# TLCduino.net
KiCad netlist of a schematic drawn in EAGLE
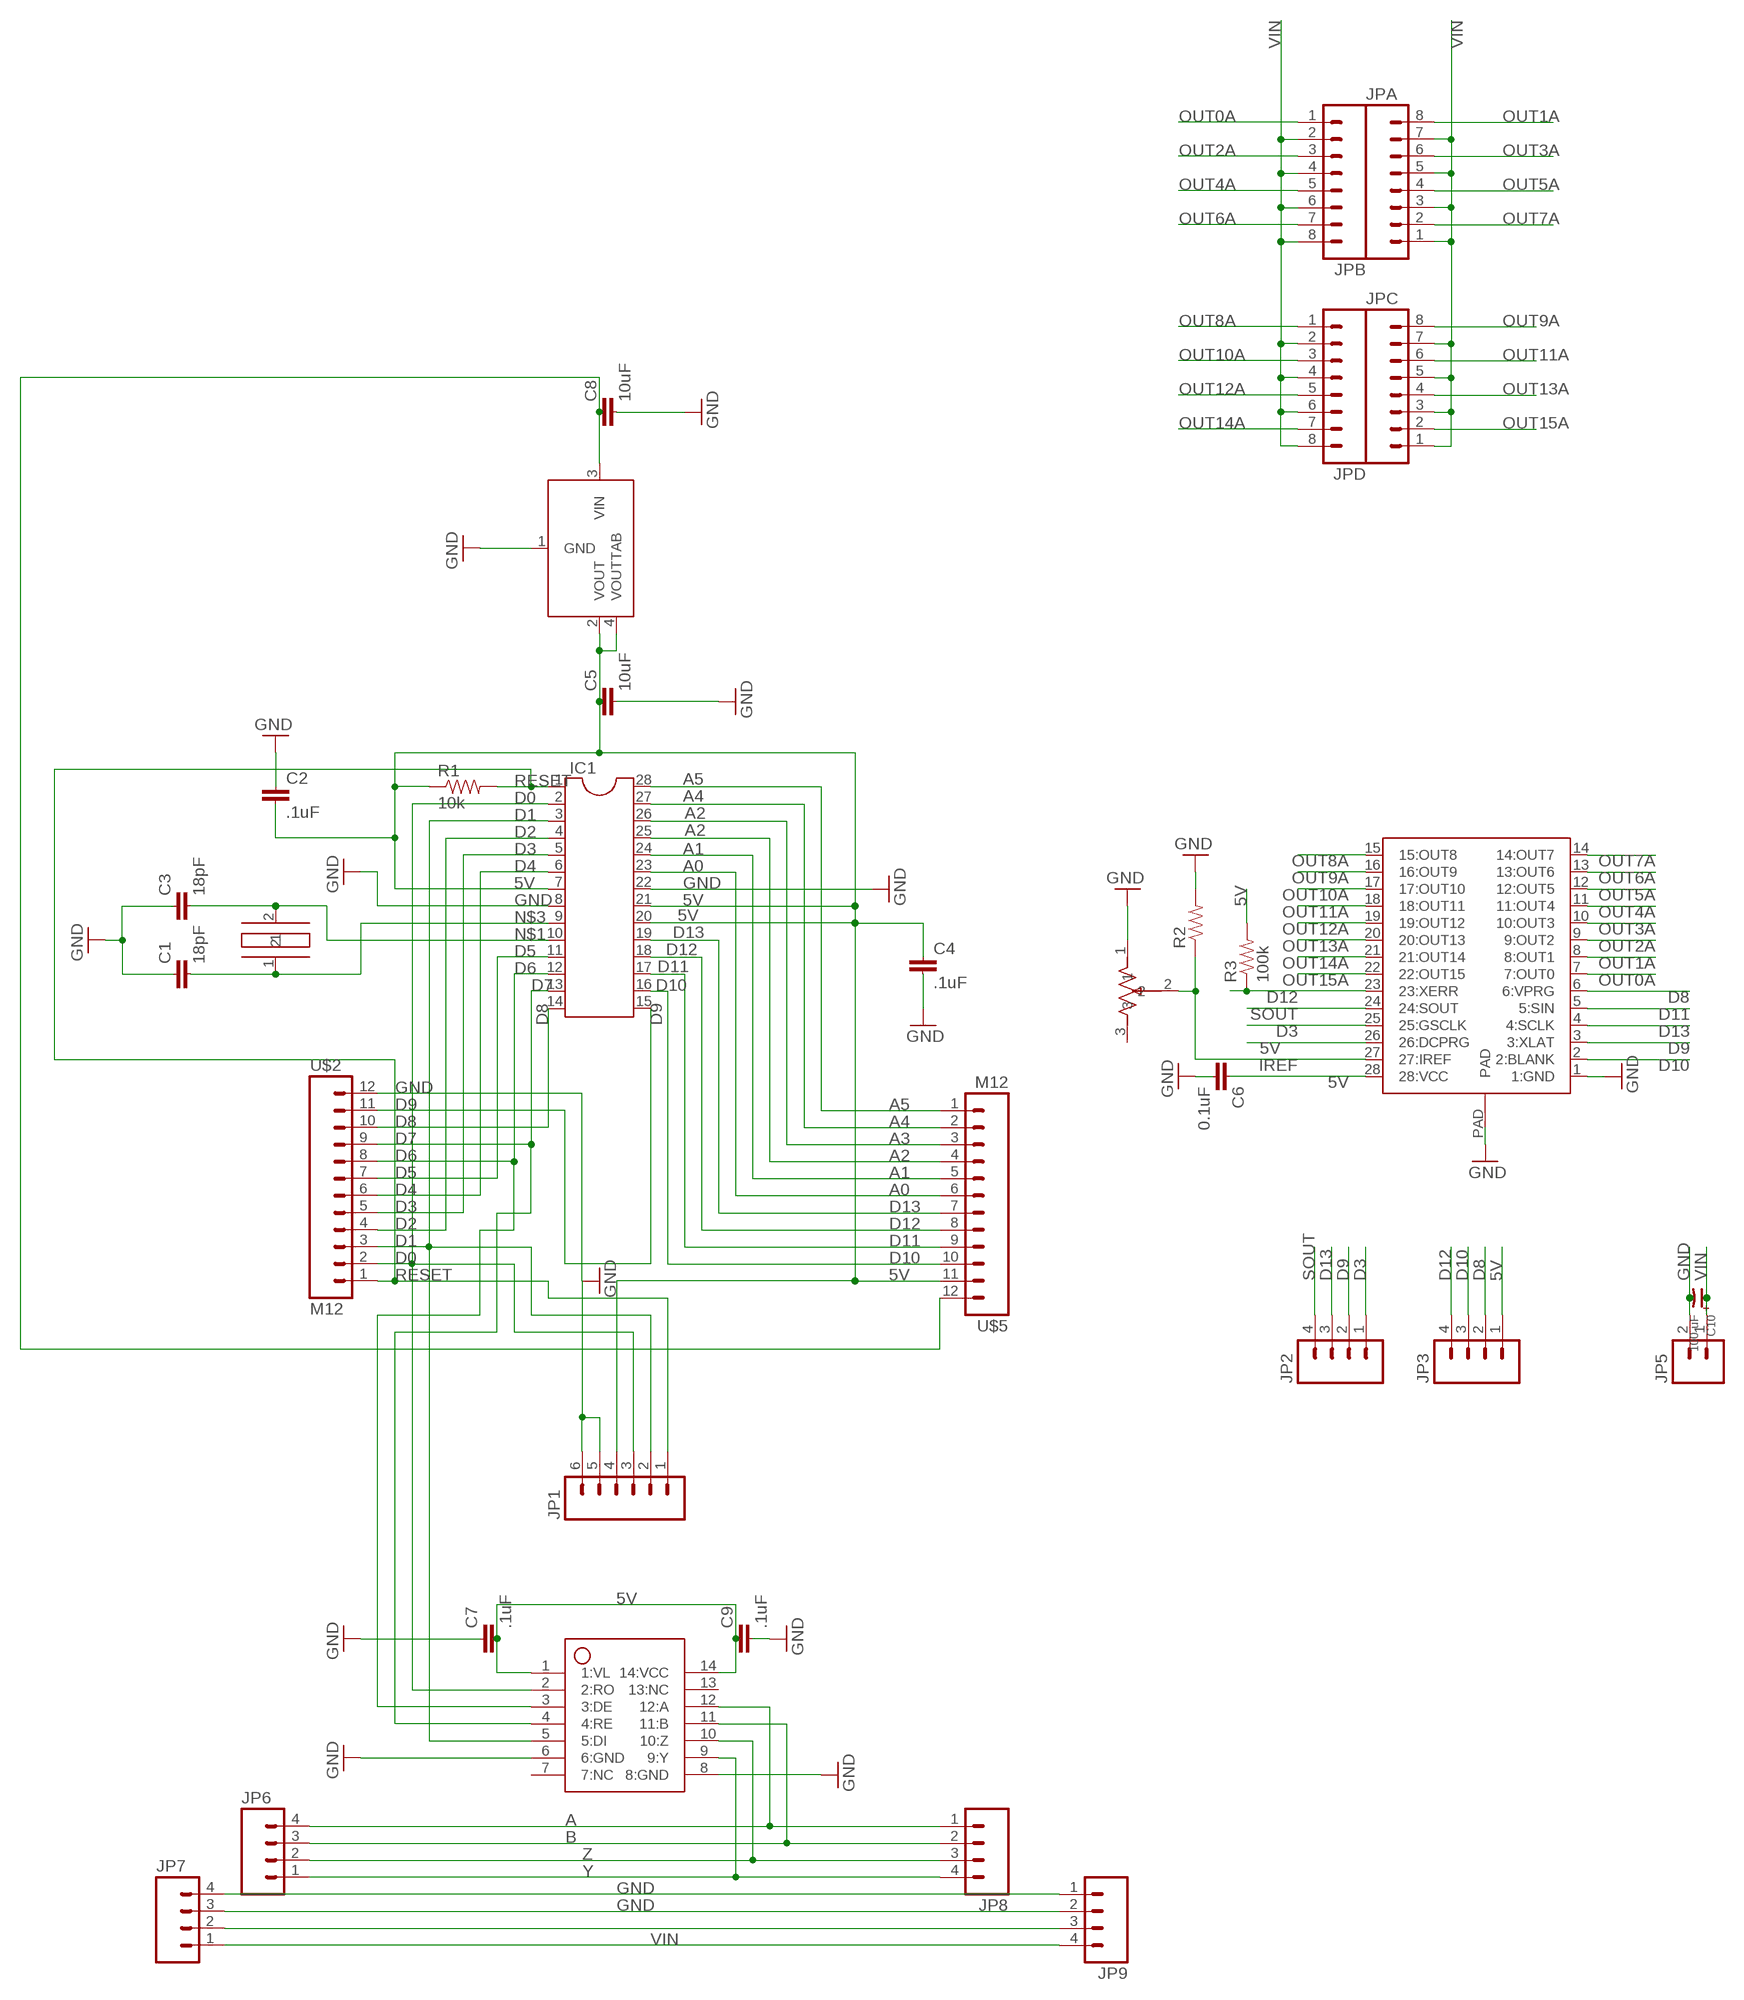
[diagram p0: schematic, sheet 1]

(export (version "E")
  (design (tool "Eeschema 10.0.6"))
  (components
    (comp (ref "5V")
      (value "ZLDO1117")
      (footprint "eagle-import:ZLDO1117")
      (libsource (lib "eagle-import") (part "ZLDO1117"))
    )
    (comp (ref "C1")
      (value "18pF")
      (footprint "eagle-import:0603-CAP")
      (libsource (lib "eagle-import") (part "CAP0603-CAP"))
    )
    (comp (ref "C2")
      (value ".1uF")
      (footprint "eagle-import:0805")
      (libsource (lib "eagle-import") (part "CAP0805"))
    )
    (comp (ref "C3")
      (value "18pF")
      (footprint "eagle-import:0603-CAP")
      (libsource (lib "eagle-import") (part "CAP0603-CAP"))
    )
    (comp (ref "C4")
      (value ".1uF")
      (footprint "eagle-import:0805")
      (libsource (lib "eagle-import") (part "CAP0805"))
    )
    (comp (ref "C5")
      (value "10uF")
      (footprint "eagle-import:1206")
      (libsource (lib "eagle-import") (part "CAP1206"))
    )
    (comp (ref "C6")
      (value "0.1uF")
      (footprint "eagle-import:0805")
      (libsource (lib "eagle-import") (part "CAP0805"))
    )
    (comp (ref "C7")
      (value ".1uF")
      (footprint "eagle-import:0805")
      (libsource (lib "eagle-import") (part "CAP0805"))
    )
    (comp (ref "C8")
      (value "10uF")
      (footprint "eagle-import:1206")
      (libsource (lib "eagle-import") (part "CAP1206"))
    )
    (comp (ref "C9")
      (value ".1uF")
      (footprint "eagle-import:0805")
      (libsource (lib "eagle-import") (part "CAP0805"))
    )
    (comp (ref "C10")
      (value "100 uF")
      (footprint "eagle-import:5X11MMCAP")
      (libsource (lib "eagle-import") (part "CAPPOL-5X11"))
    )
    (comp (ref "IC1")
      (value "DIL28-3")
      (footprint "eagle-import:DIL28-3")
      (libsource (lib "eagle-import") (part "DIL28-3"))
    )
    (comp (ref "JP1")
      (value "M06LOCK")
      (footprint "eagle-import:1X06_LOCK")
      (libsource (lib "eagle-import") (part "M06LOCK"))
    )
    (comp (ref "JP2")
      (value "M04LOCK")
      (footprint "eagle-import:1X04_LOCK")
      (libsource (lib "eagle-import") (part "M04LOCK"))
    )
    (comp (ref "JP3")
      (value "M04LOCK")
      (footprint "eagle-import:1X04_LOCK")
      (libsource (lib "eagle-import") (part "M04LOCK"))
    )
    (comp (ref "JP5")
      (value "M02LOCK")
      (footprint "eagle-import:1X02_LOCK")
      (libsource (lib "eagle-import") (part "M02LOCK"))
    )
    (comp (ref "JP6")
      (value "M04LOCK")
      (footprint "eagle-import:1X04_LOCK")
      (libsource (lib "eagle-import") (part "M04LOCK"))
    )
    (comp (ref "JP7")
      (value "M04LOCK")
      (footprint "eagle-import:1X04_LOCK")
      (libsource (lib "eagle-import") (part "M04LOCK"))
    )
    (comp (ref "JP8")
      (value "M04LOCK")
      (footprint "eagle-import:1X04_LOCK")
      (libsource (lib "eagle-import") (part "M04LOCK"))
    )
    (comp (ref "JP9")
      (value "M04LOCK")
      (footprint "eagle-import:1X04_LOCK")
      (libsource (lib "eagle-import") (part "M04LOCK"))
    )
    (comp (ref "JPA")
      (value "M08LOCK")
      (footprint "eagle-import:1X08_LOCK")
      (libsource (lib "eagle-import") (part "M08LOCK"))
    )
    (comp (ref "JPB")
      (value "M08LOCK")
      (footprint "eagle-import:1X08_LOCK")
      (libsource (lib "eagle-import") (part "M08LOCK"))
    )
    (comp (ref "JPC")
      (value "M08LOCK")
      (footprint "eagle-import:1X08_LOCK")
      (libsource (lib "eagle-import") (part "M08LOCK"))
    )
    (comp (ref "JPD")
      (value "M08LOCK")
      (footprint "eagle-import:1X08_LOCK")
      (libsource (lib "eagle-import") (part "M08LOCK"))
    )
    (comp (ref "R1")
      (value "10k")
      (footprint "eagle-import:0805")
      (libsource (lib "eagle-import") (part "RESISTOR"))
    )
    (comp (ref "R2")
      (value "RESISTOR")
      (footprint "eagle-import:0805")
      (libsource (lib "eagle-import") (part "RESISTOR"))
    )
    (comp (ref "R3")
      (value "100k")
      (footprint "eagle-import:0805")
      (libsource (lib "eagle-import") (part "RESISTOR"))
    )
    (comp (ref "U$1")
      (value "HC49US")
      (footprint "eagle-import:HC49US")
      (libsource (lib "eagle-import") (part "HC49US"))
    )
    (comp (ref "U$2")
      (value "M12")
      (footprint "eagle-import:1X12_LOCK")
      (libsource (lib "eagle-import") (part "M12LOCK"))
    )
    (comp (ref "U$3")
      (value "TLC5940")
      (footprint "eagle-import:HTSSOP-28")
      (libsource (lib "eagle-import") (part "TLC5940"))
    )
    (comp (ref "U$4")
      (value "TRIMPOTTC33X-2")
      (footprint "eagle-import:TC33X-2")
      (libsource (lib "eagle-import") (part "TRIMPOTTC33X-2"))
    )
    (comp (ref "U$5")
      (value "M12")
      (footprint "eagle-import:1X12_LOCK")
      (libsource (lib "eagle-import") (part "M12LOCK"))
    )
    (comp (ref "U$6")
      (value "MAX13432")
      (footprint "eagle-import:SO14")
      (libsource (lib "eagle-import") (part "MAX13432"))
    )
  )
  (nets
    (net (code "1") (name "/5V") (class "Default")
      (node (ref "5V") (pin "2") (pinfunction "VOUT_2") (pintype "bidirectional"))
      (node (ref "5V") (pin "4") (pinfunction "VOUTTAB_4") (pintype "bidirectional"))
      (node (ref "C2") (pin "2") (pinfunction "2_2") (pintype "passive"))
      (node (ref "C4") (pin "1") (pinfunction "1_1") (pintype "passive"))
      (node (ref "C5") (pin "1") (pinfunction "1_1") (pintype "passive"))
      (node (ref "C6") (pin "1") (pinfunction "1_1") (pintype "passive"))
      (node (ref "C7") (pin "2") (pinfunction "2_2") (pintype "passive"))
      (node (ref "C9") (pin "1") (pinfunction "1_1") (pintype "passive"))
      (node (ref "IC1") (pin "20") (pinfunction "20_20") (pintype "passive"))
      (node (ref "IC1") (pin "21") (pinfunction "21_21") (pintype "passive"))
      (node (ref "IC1") (pin "7") (pinfunction "7_7") (pintype "passive"))
      (node (ref "JP1") (pin "4") (pinfunction "4_4") (pintype "passive"))
      (node (ref "JP3") (pin "1") (pinfunction "1_1") (pintype "passive"))
      (node (ref "R1") (pin "1") (pinfunction "1_1") (pintype "passive"))
      (node (ref "R3") (pin "2") (pinfunction "2_2") (pintype "passive"))
      (node (ref "U$3") (pin "26") (pinfunction "26:DCPRG_26") (pintype "bidirectional"))
      (node (ref "U$3") (pin "28") (pinfunction "28:VCC_28") (pintype "bidirectional"))
      (node (ref "U$5") (pin "11") (pinfunction "11_11") (pintype "passive"))
      (node (ref "U$6") (pin "1") (pinfunction "1:VL_1") (pintype "bidirectional"))
      (node (ref "U$6") (pin "14") (pinfunction "14:VCC_14") (pintype "bidirectional"))
    )
    (net (code "2") (name "/A") (class "Default")
      (node (ref "JP6") (pin "4") (pinfunction "4_4") (pintype "passive"))
      (node (ref "JP8") (pin "1") (pinfunction "1_1") (pintype "passive"))
      (node (ref "U$6") (pin "12") (pinfunction "12:A_12") (pintype "bidirectional"))
    )
    (net (code "3") (name "/A0") (class "Default")
      (node (ref "IC1") (pin "23") (pinfunction "23_23") (pintype "passive"))
      (node (ref "U$5") (pin "6") (pinfunction "6_6") (pintype "passive"))
    )
    (net (code "4") (name "/A1") (class "Default")
      (node (ref "IC1") (pin "24") (pinfunction "24_24") (pintype "passive"))
      (node (ref "U$5") (pin "5") (pinfunction "5_5") (pintype "passive"))
    )
    (net (code "5") (name "/A2") (class "Default")
      (node (ref "IC1") (pin "25") (pinfunction "25_25") (pintype "passive"))
      (node (ref "U$5") (pin "4") (pinfunction "4_4") (pintype "passive"))
    )
    (net (code "6") (name "/A3") (class "Default")
      (node (ref "IC1") (pin "26") (pinfunction "26_26") (pintype "passive"))
      (node (ref "U$5") (pin "3") (pinfunction "3_3") (pintype "passive"))
    )
    (net (code "7") (name "/A4") (class "Default")
      (node (ref "IC1") (pin "27") (pinfunction "27_27") (pintype "passive"))
      (node (ref "U$5") (pin "2") (pinfunction "2_2") (pintype "passive"))
    )
    (net (code "8") (name "/A5") (class "Default")
      (node (ref "IC1") (pin "28") (pinfunction "28_28") (pintype "passive"))
      (node (ref "U$5") (pin "1") (pinfunction "1_1") (pintype "passive"))
    )
    (net (code "9") (name "/B") (class "Default")
      (node (ref "JP6") (pin "3") (pinfunction "3_3") (pintype "passive"))
      (node (ref "JP8") (pin "2") (pinfunction "2_2") (pintype "passive"))
      (node (ref "U$6") (pin "11") (pinfunction "11:B_11") (pintype "bidirectional"))
    )
    (net (code "10") (name "/D0") (class "Default")
      (node (ref "IC1") (pin "2") (pinfunction "2_2") (pintype "passive"))
      (node (ref "JP1") (pin "3") (pinfunction "3_3") (pintype "passive"))
      (node (ref "U$2") (pin "2") (pinfunction "2_2") (pintype "passive"))
      (node (ref "U$6") (pin "2") (pinfunction "2:RO_2") (pintype "bidirectional"))
    )
    (net (code "11") (name "/D1") (class "Default")
      (node (ref "IC1") (pin "3") (pinfunction "3_3") (pintype "passive"))
      (node (ref "JP1") (pin "2") (pinfunction "2_2") (pintype "passive"))
      (node (ref "U$2") (pin "3") (pinfunction "3_3") (pintype "passive"))
      (node (ref "U$6") (pin "5") (pinfunction "5:DI_5") (pintype "bidirectional"))
    )
    (net (code "12") (name "/D2") (class "Default")
      (node (ref "IC1") (pin "4") (pinfunction "4_4") (pintype "passive"))
      (node (ref "U$2") (pin "4") (pinfunction "4_4") (pintype "passive"))
    )
    (net (code "13") (name "/D3") (class "Default")
      (node (ref "IC1") (pin "5") (pinfunction "5_5") (pintype "passive"))
      (node (ref "JP2") (pin "1") (pinfunction "1_1") (pintype "passive"))
      (node (ref "U$2") (pin "5") (pinfunction "5_5") (pintype "passive"))
      (node (ref "U$3") (pin "25") (pinfunction "25:GSCLK_25") (pintype "bidirectional"))
    )
    (net (code "14") (name "/D4") (class "Default")
      (node (ref "IC1") (pin "6") (pinfunction "6_6") (pintype "passive"))
      (node (ref "U$2") (pin "6") (pinfunction "6_6") (pintype "passive"))
    )
    (net (code "15") (name "/D5") (class "Default")
      (node (ref "IC1") (pin "11") (pinfunction "11_11") (pintype "passive"))
      (node (ref "U$2") (pin "7") (pinfunction "7_7") (pintype "passive"))
    )
    (net (code "16") (name "/D6") (class "Default")
      (node (ref "IC1") (pin "12") (pinfunction "12_12") (pintype "passive"))
      (node (ref "U$2") (pin "8") (pinfunction "8_8") (pintype "passive"))
      (node (ref "U$6") (pin "3") (pinfunction "3:DE_3") (pintype "bidirectional"))
    )
    (net (code "17") (name "/D7") (class "Default")
      (node (ref "IC1") (pin "13") (pinfunction "13_13") (pintype "passive"))
      (node (ref "U$2") (pin "9") (pinfunction "9_9") (pintype "passive"))
      (node (ref "U$6") (pin "4") (pinfunction "4:RE_4") (pintype "bidirectional"))
    )
    (net (code "18") (name "/D8") (class "Default")
      (node (ref "IC1") (pin "14") (pinfunction "14_14") (pintype "passive"))
      (node (ref "JP3") (pin "2") (pinfunction "2_2") (pintype "passive"))
      (node (ref "U$2") (pin "10") (pinfunction "10_10") (pintype "passive"))
      (node (ref "U$3") (pin "6") (pinfunction "6:VPRG_6") (pintype "bidirectional"))
    )
    (net (code "19") (name "/D9") (class "Default")
      (node (ref "IC1") (pin "15") (pinfunction "15_15") (pintype "passive"))
      (node (ref "JP2") (pin "2") (pinfunction "2_2") (pintype "passive"))
      (node (ref "U$2") (pin "11") (pinfunction "11_11") (pintype "passive"))
      (node (ref "U$3") (pin "3") (pinfunction "3:XLAT_3") (pintype "bidirectional"))
    )
    (net (code "20") (name "/D10") (class "Default")
      (node (ref "IC1") (pin "16") (pinfunction "16_16") (pintype "passive"))
      (node (ref "JP3") (pin "3") (pinfunction "3_3") (pintype "passive"))
      (node (ref "U$3") (pin "2") (pinfunction "2:BLANK_2") (pintype "bidirectional"))
      (node (ref "U$5") (pin "10") (pinfunction "10_10") (pintype "passive"))
    )
    (net (code "21") (name "/D11") (class "Default")
      (node (ref "IC1") (pin "17") (pinfunction "17_17") (pintype "passive"))
      (node (ref "U$3") (pin "5") (pinfunction "5:SIN_5") (pintype "bidirectional"))
      (node (ref "U$5") (pin "9") (pinfunction "9_9") (pintype "passive"))
    )
    (net (code "22") (name "/D12") (class "Default")
      (node (ref "IC1") (pin "18") (pinfunction "18_18") (pintype "passive"))
      (node (ref "JP3") (pin "4") (pinfunction "4_4") (pintype "passive"))
      (node (ref "R3") (pin "1") (pinfunction "1_1") (pintype "passive"))
      (node (ref "U$3") (pin "23") (pinfunction "23:XERR_23") (pintype "bidirectional"))
      (node (ref "U$5") (pin "8") (pinfunction "8_8") (pintype "passive"))
    )
    (net (code "23") (name "/D13") (class "Default")
      (node (ref "IC1") (pin "19") (pinfunction "19_19") (pintype "passive"))
      (node (ref "JP2") (pin "3") (pinfunction "3_3") (pintype "passive"))
      (node (ref "U$3") (pin "4") (pinfunction "4:SCLK_4") (pintype "bidirectional"))
      (node (ref "U$5") (pin "7") (pinfunction "7_7") (pintype "passive"))
    )
    (net (code "24") (name "/IREF") (class "Default")
      (node (ref "R2") (pin "1") (pinfunction "1_1") (pintype "passive"))
      (node (ref "U$3") (pin "27") (pinfunction "27:IREF_27") (pintype "bidirectional"))
      (node (ref "U$4") (pin "2") (pinfunction "2_2") (pintype "bidirectional"))
    )
    (net (code "25") (name "/N$1") (class "Default")
      (node (ref "C3") (pin "2") (pinfunction "2_2") (pintype "passive"))
      (node (ref "IC1") (pin "10") (pinfunction "10_10") (pintype "passive"))
      (node (ref "U$1") (pin "2") (pinfunction "2_2") (pintype "bidirectional"))
    )
    (net (code "26") (name "/N$3") (class "Default")
      (node (ref "C1") (pin "2") (pinfunction "2_2") (pintype "passive"))
      (node (ref "IC1") (pin "9") (pinfunction "9_9") (pintype "passive"))
      (node (ref "U$1") (pin "1") (pinfunction "1_1") (pintype "bidirectional"))
    )
    (net (code "27") (name "/OUT0A") (class "Default")
      (node (ref "JPB") (pin "1") (pinfunction "1_1") (pintype "passive"))
      (node (ref "U$3") (pin "7") (pinfunction "7:OUT0_7") (pintype "bidirectional"))
    )
    (net (code "28") (name "/OUT1A") (class "Default")
      (node (ref "JPA") (pin "8") (pinfunction "8_8") (pintype "passive"))
      (node (ref "U$3") (pin "8") (pinfunction "8:OUT1_8") (pintype "bidirectional"))
    )
    (net (code "29") (name "/OUT2A") (class "Default")
      (node (ref "JPB") (pin "3") (pinfunction "3_3") (pintype "passive"))
      (node (ref "U$3") (pin "9") (pinfunction "9:OUT2_9") (pintype "bidirectional"))
    )
    (net (code "30") (name "/OUT3A") (class "Default")
      (node (ref "JPA") (pin "6") (pinfunction "6_6") (pintype "passive"))
      (node (ref "U$3") (pin "10") (pinfunction "10:OUT3_10") (pintype "bidirectional"))
    )
    (net (code "31") (name "/OUT4A") (class "Default")
      (node (ref "JPB") (pin "5") (pinfunction "5_5") (pintype "passive"))
      (node (ref "U$3") (pin "11") (pinfunction "11:OUT4_11") (pintype "bidirectional"))
    )
    (net (code "32") (name "/OUT5A") (class "Default")
      (node (ref "JPA") (pin "4") (pinfunction "4_4") (pintype "passive"))
      (node (ref "U$3") (pin "12") (pinfunction "12:OUT5_12") (pintype "bidirectional"))
    )
    (net (code "33") (name "/OUT6A") (class "Default")
      (node (ref "JPB") (pin "7") (pinfunction "7_7") (pintype "passive"))
      (node (ref "U$3") (pin "13") (pinfunction "13:OUT6_13") (pintype "bidirectional"))
    )
    (net (code "34") (name "/OUT7A") (class "Default")
      (node (ref "JPA") (pin "2") (pinfunction "2_2") (pintype "passive"))
      (node (ref "U$3") (pin "14") (pinfunction "14:OUT7_14") (pintype "bidirectional"))
    )
    (net (code "35") (name "/OUT8A") (class "Default")
      (node (ref "JPD") (pin "1") (pinfunction "1_1") (pintype "passive"))
      (node (ref "U$3") (pin "15") (pinfunction "15:OUT8_15") (pintype "bidirectional"))
    )
    (net (code "36") (name "/OUT9A") (class "Default")
      (node (ref "JPC") (pin "8") (pinfunction "8_8") (pintype "passive"))
      (node (ref "U$3") (pin "16") (pinfunction "16:OUT9_16") (pintype "bidirectional"))
    )
    (net (code "37") (name "/OUT10A") (class "Default")
      (node (ref "JPD") (pin "3") (pinfunction "3_3") (pintype "passive"))
      (node (ref "U$3") (pin "17") (pinfunction "17:OUT10_17") (pintype "bidirectional"))
    )
    (net (code "38") (name "/OUT11A") (class "Default")
      (node (ref "JPC") (pin "6") (pinfunction "6_6") (pintype "passive"))
      (node (ref "U$3") (pin "18") (pinfunction "18:OUT11_18") (pintype "bidirectional"))
    )
    (net (code "39") (name "/OUT12A") (class "Default")
      (node (ref "JPD") (pin "5") (pinfunction "5_5") (pintype "passive"))
      (node (ref "U$3") (pin "19") (pinfunction "19:OUT12_19") (pintype "bidirectional"))
    )
    (net (code "40") (name "/OUT13A") (class "Default")
      (node (ref "JPC") (pin "4") (pinfunction "4_4") (pintype "passive"))
      (node (ref "U$3") (pin "20") (pinfunction "20:OUT13_20") (pintype "bidirectional"))
    )
    (net (code "41") (name "/OUT14A") (class "Default")
      (node (ref "JPD") (pin "7") (pinfunction "7_7") (pintype "passive"))
      (node (ref "U$3") (pin "21") (pinfunction "21:OUT14_21") (pintype "bidirectional"))
    )
    (net (code "42") (name "/OUT15A") (class "Default")
      (node (ref "JPC") (pin "2") (pinfunction "2_2") (pintype "passive"))
      (node (ref "U$3") (pin "22") (pinfunction "22:OUT15_22") (pintype "bidirectional"))
    )
    (net (code "43") (name "/RESET") (class "Default")
      (node (ref "IC1") (pin "1") (pinfunction "1_1") (pintype "passive"))
      (node (ref "JP1") (pin "1") (pinfunction "1_1") (pintype "passive"))
      (node (ref "R1") (pin "2") (pinfunction "2_2") (pintype "passive"))
      (node (ref "U$2") (pin "1") (pinfunction "1_1") (pintype "passive"))
    )
    (net (code "44") (name "/SOUT") (class "Default")
      (node (ref "JP2") (pin "4") (pinfunction "4_4") (pintype "passive"))
      (node (ref "U$3") (pin "24") (pinfunction "24:SOUT_24") (pintype "bidirectional"))
    )
    (net (code "45") (name "/VIN") (class "Default")
      (node (ref "5V") (pin "3") (pinfunction "VIN_3") (pintype "bidirectional"))
      (node (ref "C10") (pin "+") (pinfunction "+_+") (pintype "bidirectional"))
      (node (ref "C8") (pin "1") (pinfunction "1_1") (pintype "passive"))
      (node (ref "JP5") (pin "1") (pinfunction "1_1") (pintype "passive"))
      (node (ref "JP7") (pin "1") (pinfunction "1_1") (pintype "passive"))
      (node (ref "JP7") (pin "2") (pinfunction "2_2") (pintype "passive"))
      (node (ref "JP9") (pin "3") (pinfunction "3_3") (pintype "passive"))
      (node (ref "JP9") (pin "4") (pinfunction "4_4") (pintype "passive"))
      (node (ref "JPA") (pin "1") (pinfunction "1_1") (pintype "passive"))
      (node (ref "JPA") (pin "3") (pinfunction "3_3") (pintype "passive"))
      (node (ref "JPA") (pin "5") (pinfunction "5_5") (pintype "passive"))
      (node (ref "JPA") (pin "7") (pinfunction "7_7") (pintype "passive"))
      (node (ref "JPB") (pin "2") (pinfunction "2_2") (pintype "passive"))
      (node (ref "JPB") (pin "4") (pinfunction "4_4") (pintype "passive"))
      (node (ref "JPB") (pin "6") (pinfunction "6_6") (pintype "passive"))
      (node (ref "JPB") (pin "8") (pinfunction "8_8") (pintype "passive"))
      (node (ref "JPC") (pin "1") (pinfunction "1_1") (pintype "passive"))
      (node (ref "JPC") (pin "3") (pinfunction "3_3") (pintype "passive"))
      (node (ref "JPC") (pin "5") (pinfunction "5_5") (pintype "passive"))
      (node (ref "JPC") (pin "7") (pinfunction "7_7") (pintype "passive"))
      (node (ref "JPD") (pin "2") (pinfunction "2_2") (pintype "passive"))
      (node (ref "JPD") (pin "4") (pinfunction "4_4") (pintype "passive"))
      (node (ref "JPD") (pin "6") (pinfunction "6_6") (pintype "passive"))
      (node (ref "JPD") (pin "8") (pinfunction "8_8") (pintype "passive"))
      (node (ref "U$5") (pin "12") (pinfunction "12_12") (pintype "passive"))
    )
    (net (code "46") (name "/Y") (class "Default")
      (node (ref "JP6") (pin "1") (pinfunction "1_1") (pintype "passive"))
      (node (ref "JP8") (pin "4") (pinfunction "4_4") (pintype "passive"))
      (node (ref "U$6") (pin "9") (pinfunction "9:Y_9") (pintype "bidirectional"))
    )
    (net (code "47") (name "/Z") (class "Default")
      (node (ref "JP6") (pin "2") (pinfunction "2_2") (pintype "passive"))
      (node (ref "JP8") (pin "3") (pinfunction "3_3") (pintype "passive"))
      (node (ref "U$6") (pin "10") (pinfunction "10:Z_10") (pintype "bidirectional"))
    )
    (net (code "48") (name "GND") (class "Default")
      (node (ref "5V") (pin "1") (pinfunction "GND_1") (pintype "bidirectional"))
      (node (ref "C1") (pin "1") (pinfunction "1_1") (pintype "passive"))
      (node (ref "C10") (pin "-") (pinfunction "-_-") (pintype "bidirectional"))
      (node (ref "C2") (pin "1") (pinfunction "1_1") (pintype "passive"))
      (node (ref "C3") (pin "1") (pinfunction "1_1") (pintype "passive"))
      (node (ref "C4") (pin "2") (pinfunction "2_2") (pintype "passive"))
      (node (ref "C5") (pin "2") (pinfunction "2_2") (pintype "passive"))
      (node (ref "C6") (pin "2") (pinfunction "2_2") (pintype "passive"))
      (node (ref "C7") (pin "1") (pinfunction "1_1") (pintype "passive"))
      (node (ref "C8") (pin "2") (pinfunction "2_2") (pintype "passive"))
      (node (ref "C9") (pin "2") (pinfunction "2_2") (pintype "passive"))
      (node (ref "IC1") (pin "22") (pinfunction "22_22") (pintype "passive"))
      (node (ref "IC1") (pin "8") (pinfunction "8_8") (pintype "passive"))
      (node (ref "JP1") (pin "5") (pinfunction "5_5") (pintype "passive"))
      (node (ref "JP1") (pin "6") (pinfunction "6_6") (pintype "passive"))
      (node (ref "JP5") (pin "2") (pinfunction "2_2") (pintype "passive"))
      (node (ref "JP7") (pin "3") (pinfunction "3_3") (pintype "passive"))
      (node (ref "JP7") (pin "4") (pinfunction "4_4") (pintype "passive"))
      (node (ref "JP9") (pin "1") (pinfunction "1_1") (pintype "passive"))
      (node (ref "JP9") (pin "2") (pinfunction "2_2") (pintype "passive"))
      (node (ref "R2") (pin "2") (pinfunction "2_2") (pintype "passive"))
      (node (ref "U$2") (pin "12") (pinfunction "12_12") (pintype "passive"))
      (node (ref "U$3") (pin "1") (pinfunction "1:GND_1") (pintype "bidirectional"))
      (node (ref "U$3") (pin "PAD") (pinfunction "PAD_PAD") (pintype "bidirectional"))
      (node (ref "U$4") (pin "1") (pinfunction "1_1") (pintype "bidirectional"))
      (node (ref "U$6") (pin "6") (pinfunction "6:GND_6") (pintype "bidirectional"))
      (node (ref "U$6") (pin "8") (pinfunction "8:GND_8") (pintype "bidirectional"))
    )
    (net (code "49") (name "unconnected-(U$4-Pad3)") (class "Default")
      (node (ref "U$4") (pin "3") (pinfunction "3_3") (pintype "bidirectional"))
    )
    (net (code "50") (name "unconnected-(U$6-7:NC-Pad7)") (class "Default")
      (node (ref "U$6") (pin "7") (pinfunction "7:NC_7") (pintype "bidirectional"))
    )
    (net (code "51") (name "unconnected-(U$6-13:NC-Pad13)") (class "Default")
      (node (ref "U$6") (pin "13") (pinfunction "13:NC_13") (pintype "bidirectional"))
    )
  )
)
